# 201944AEP4P02.net
KiCad netlist of a schematic drawn in Altium Designer
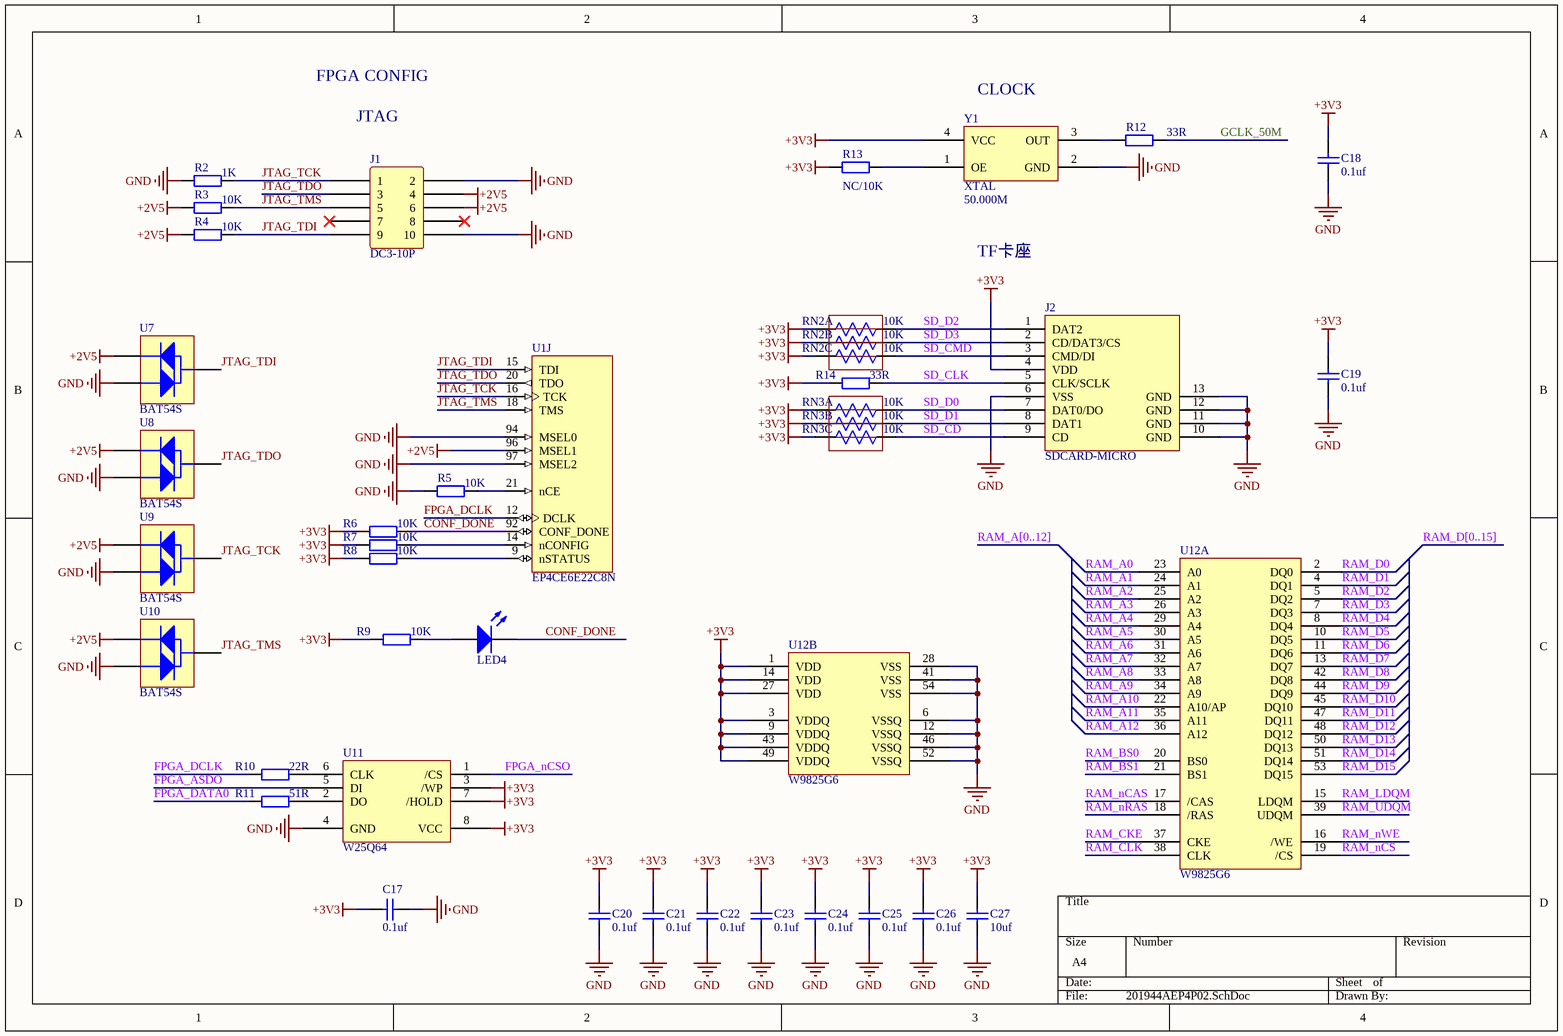
[diagram p0: 201944AEP4P02.SchDoc]

(export (version "E")
  (design (tool "Eeschema 10.0.6"))
  (components
    (comp (ref "C17")
      (value "0.1uf")
      (footprint "C0805")
      (fields (field (name "Comment") "Cap"))
      (libsource (lib "carrot_lib") (part "Cap"))
    )
    (comp (ref "C18")
      (value "0.1uf")
      (footprint "C0805")
      (fields (field (name "Comment") "Cap"))
      (libsource (lib "carrot_lib") (part "Cap"))
    )
    (comp (ref "C19")
      (value "0.1uf")
      (footprint "C0805")
      (fields (field (name "Comment") "Cap"))
      (libsource (lib "carrot_lib") (part "Cap"))
    )
    (comp (ref "C20")
      (value "0.1uf")
      (footprint "C0805")
      (fields (field (name "Comment") "Cap"))
      (libsource (lib "carrot_lib") (part "Cap"))
    )
    (comp (ref "C21")
      (value "0.1uf")
      (footprint "C0805")
      (fields (field (name "Comment") "Cap"))
      (libsource (lib "carrot_lib") (part "Cap"))
    )
    (comp (ref "C22")
      (value "0.1uf")
      (footprint "C0805")
      (fields (field (name "Comment") "Cap"))
      (libsource (lib "carrot_lib") (part "Cap"))
    )
    (comp (ref "C23")
      (value "0.1uf")
      (footprint "C0805")
      (fields (field (name "Comment") "Cap"))
      (libsource (lib "carrot_lib") (part "Cap"))
    )
    (comp (ref "C24")
      (value "0.1uf")
      (footprint "C0805")
      (fields (field (name "Comment") "Cap"))
      (libsource (lib "carrot_lib") (part "Cap"))
    )
    (comp (ref "C25")
      (value "0.1uf")
      (footprint "C0805")
      (fields (field (name "Comment") "Cap"))
      (libsource (lib "carrot_lib") (part "Cap"))
    )
    (comp (ref "C26")
      (value "0.1uf")
      (footprint "C0805")
      (fields (field (name "Comment") "Cap"))
      (libsource (lib "carrot_lib") (part "Cap"))
    )
    (comp (ref "C27")
      (value "10uf")
      (footprint "C0805")
      (fields (field (name "Comment") "Cap"))
      (libsource (lib "carrot_lib") (part "Cap"))
    )
    (comp (ref "J1") (value "DC3-10P") (footprint "DC3-10P") (libsource (lib "carrot_lib") (part "DC3-10P")))
    (comp (ref "J2")
      (value "SDCARD-MICRO")
      (footprint "SDCARD-MICRO")
      (description "Micro SD卡座")
      (libsource (lib "carrot_lib") (part "SDCARD-MICRO"))
    )
    (comp (ref "LED4") (value "LED") (footprint "LED1206") (libsource (lib "carrot_lib") (part "LED")))
    (comp (ref "R2")
      (value "1K")
      (footprint "R0805")
      (fields (field (name "Comment") "Res"))
      (libsource (lib "carrot_lib") (part "Res"))
    )
    (comp (ref "R3")
      (value "10K")
      (footprint "R0805")
      (fields (field (name "Comment") "Res"))
      (libsource (lib "carrot_lib") (part "Res"))
    )
    (comp (ref "R4")
      (value "10K")
      (footprint "R0805")
      (fields (field (name "Comment") "Res"))
      (libsource (lib "carrot_lib") (part "Res"))
    )
    (comp (ref "R5")
      (value "10K")
      (footprint "R0805")
      (fields (field (name "Comment") "Res"))
      (libsource (lib "carrot_lib") (part "Res"))
    )
    (comp (ref "R6")
      (value "10K")
      (footprint "R0805")
      (fields (field (name "Comment") "Res"))
      (libsource (lib "carrot_lib") (part "Res"))
    )
    (comp (ref "R7")
      (value "10K")
      (footprint "R0805")
      (fields (field (name "Comment") "Res"))
      (libsource (lib "carrot_lib") (part "Res"))
    )
    (comp (ref "R8")
      (value "10K")
      (footprint "R0805")
      (fields (field (name "Comment") "Res"))
      (libsource (lib "carrot_lib") (part "Res"))
    )
    (comp (ref "R9")
      (value "10K")
      (footprint "R0805")
      (fields (field (name "Comment") "Res"))
      (libsource (lib "carrot_lib") (part "Res"))
    )
    (comp (ref "R10")
      (value "22R")
      (footprint "R0805")
      (fields (field (name "Comment") "Res"))
      (libsource (lib "carrot_lib") (part "Res"))
    )
    (comp (ref "R11")
      (value "51R")
      (footprint "R0805")
      (fields (field (name "Comment") "Res"))
      (libsource (lib "carrot_lib") (part "Res"))
    )
    (comp (ref "R12")
      (value "33R")
      (footprint "R0805")
      (fields (field (name "Comment") "Res"))
      (libsource (lib "carrot_lib") (part "Res"))
    )
    (comp (ref "R13")
      (value "NC/10K")
      (footprint "R0805")
      (fields (field (name "Comment") "Res"))
      (libsource (lib "carrot_lib") (part "Res"))
    )
    (comp (ref "R14")
      (value "33R")
      (footprint "R0805")
      (fields (field (name "Comment") "Res"))
      (libsource (lib "carrot_lib") (part "Res"))
    )
    (comp (ref "RN2")
      (value "10K")
      (footprint "RA0603")
      (description "贴片排阻")
      (fields (field (name "Comment") "Res Array"))
      (libsource (lib "carrot_lib") (part "Res Array 2"))
    )
    (comp (ref "RN3")
      (value "10K")
      (footprint "RA0603")
      (description "贴片排阻")
      (fields (field (name "Comment") "Res Array"))
      (libsource (lib "carrot_lib") (part "Res Array 2"))
    )
    (comp (ref "U1")
      (value "EP4CE6E22C8N")
      (footprint "EP4CE6E22C8N-EQFP144+")
      (fields (field (name "MANUFACTURER") "Altera"))
      (libsource (lib "carrot_lib") (part "EP4CE6E22C8N"))
    )
    (comp (ref "U7")
      (value "BAT54S")
      (footprint "BAT54S-SOT23")
      (libsource (lib "carrot_lib") (part "BAT54S"))
    )
    (comp (ref "U8")
      (value "BAT54S")
      (footprint "BAT54S-SOT23")
      (libsource (lib "carrot_lib") (part "BAT54S"))
    )
    (comp (ref "U9")
      (value "BAT54S")
      (footprint "BAT54S-SOT23")
      (libsource (lib "carrot_lib") (part "BAT54S"))
    )
    (comp (ref "U10")
      (value "BAT54S")
      (footprint "BAT54S-SOT23")
      (libsource (lib "carrot_lib") (part "BAT54S"))
    )
    (comp (ref "U11")
      (value "W25Q64")
      (footprint "W25Q64-SOIC8")
      (description "64M-BIT\r\nSERIAL FLASH MEMORY WITH\r\nDUAL, QUAD SPI")
      (fields (field (name "MANUFACTURER") "Microchip") (field (name "PARTNUMBER") "24LC256-I/SN"))
      (libsource (lib "carrot_lib") (part "W25Q64"))
    )
    (comp (ref "U12")
      (value "W9825G6")
      (footprint "W9825G6-TSOP54")
      (description "4 M * 4 BANKS * 16 BITS SDRAM")
      (libsource (lib "carrot_lib") (part "W9825G6"))
    )
    (comp (ref "Y1")
      (value "XTAL")
      (footprint "XTAL-3225")
      (description "有源晶振")
      (fields (field (name "ALTIUM_VALUE") "50.000M"))
      (libsource (lib "carrot_lib") (part "XTAL2"))
    )
  )
  (nets
    (net (code "1") (name "+2V5") (class "Default")
      (node (ref "J1") (pin "4") (pinfunction "4_4") (pintype "passive"))
      (node (ref "J1") (pin "6") (pinfunction "6_6") (pintype "passive"))
      (node (ref "R3") (pin "1") (pinfunction "1_1") (pintype "passive"))
      (node (ref "R4") (pin "1") (pinfunction "1_1") (pintype "passive"))
      (node (ref "U1") (pin "96") (pinfunction "MSEL1_96") (pintype "input"))
      (node (ref "U10") (pin "B") (pinfunction "B_B") (pintype "passive"))
      (node (ref "U7") (pin "B") (pinfunction "B_B") (pintype "passive"))
      (node (ref "U8") (pin "B") (pinfunction "B_B") (pintype "passive"))
      (node (ref "U9") (pin "B") (pinfunction "B_B") (pintype "passive"))
    )
    (net (code "2") (name "+3V3") (class "Default")
      (node (ref "C17") (pin "1") (pinfunction "1_1") (pintype "passive"))
      (node (ref "C18") (pin "1") (pinfunction "1_1") (pintype "passive"))
      (node (ref "C19") (pin "1") (pinfunction "1_1") (pintype "passive"))
      (node (ref "C20") (pin "1") (pinfunction "1_1") (pintype "passive"))
      (node (ref "C21") (pin "1") (pinfunction "1_1") (pintype "passive"))
      (node (ref "C22") (pin "1") (pinfunction "1_1") (pintype "passive"))
      (node (ref "C23") (pin "1") (pinfunction "1_1") (pintype "passive"))
      (node (ref "C24") (pin "1") (pinfunction "1_1") (pintype "passive"))
      (node (ref "C25") (pin "1") (pinfunction "1_1") (pintype "passive"))
      (node (ref "C26") (pin "1") (pinfunction "1_1") (pintype "passive"))
      (node (ref "C27") (pin "1") (pinfunction "1_1") (pintype "passive"))
      (node (ref "J2") (pin "4") (pinfunction "VDD_4") (pintype "passive"))
      (node (ref "R13") (pin "1") (pinfunction "1_1") (pintype "passive"))
      (node (ref "R14") (pin "1") (pinfunction "1_1") (pintype "passive"))
      (node (ref "R6") (pin "1") (pinfunction "1_1") (pintype "passive"))
      (node (ref "R7") (pin "1") (pinfunction "1_1") (pintype "passive"))
      (node (ref "R8") (pin "1") (pinfunction "1_1") (pintype "passive"))
      (node (ref "R9") (pin "1") (pinfunction "1_1") (pintype "passive"))
      (node (ref "RN2") (pin "1") (pinfunction "1_1") (pintype "passive"))
      (node (ref "RN2") (pin "2") (pinfunction "2_2") (pintype "passive"))
      (node (ref "RN2") (pin "3") (pinfunction "3_3") (pintype "passive"))
      (node (ref "RN3") (pin "1") (pinfunction "1_1") (pintype "passive"))
      (node (ref "RN3") (pin "2") (pinfunction "2_2") (pintype "passive"))
      (node (ref "RN3") (pin "3") (pinfunction "3_3") (pintype "passive"))
      (node (ref "U11") (pin "3") (pinfunction "/WP_3") (pintype "passive"))
      (node (ref "U11") (pin "7") (pinfunction "/HOLD_7") (pintype "passive"))
      (node (ref "U11") (pin "8") (pinfunction "VCC_8") (pintype "passive"))
      (node (ref "U12") (pin "1") (pinfunction "VDD_1") (pintype "passive"))
      (node (ref "U12") (pin "14") (pinfunction "VDD_14") (pintype "passive"))
      (node (ref "U12") (pin "27") (pinfunction "VDD_27") (pintype "passive"))
      (node (ref "U12") (pin "3") (pinfunction "VDDQ_3") (pintype "passive"))
      (node (ref "U12") (pin "43") (pinfunction "VDDQ_43") (pintype "passive"))
      (node (ref "U12") (pin "49") (pinfunction "VDDQ_49") (pintype "passive"))
      (node (ref "U12") (pin "9") (pinfunction "VDDQ_9") (pintype "passive"))
      (node (ref "Y1") (pin "4") (pinfunction "VCC_4") (pintype "passive"))
    )
    (net (code "3") (name "/CONF_DONE") (class "Default")
      (node (ref "LED4") (pin "2") (pinfunction "K_2") (pintype "passive"))
      (node (ref "R6") (pin "2") (pinfunction "2_2") (pintype "passive"))
      (node (ref "U1") (pin "92") (pinfunction "CONF_DONE_92") (pintype "bidirectional"))
    )
    (net (code "4") (name "/FPGA_ASDO") (class "Default")
      (node (ref "U11") (pin "5") (pinfunction "DI_5") (pintype "passive"))
    )
    (net (code "5") (name "/FPGA_DATA0") (class "Default")
      (node (ref "R11") (pin "1") (pinfunction "1_1") (pintype "passive"))
    )
    (net (code "6") (name "/FPGA_DCLK") (class "Default")
      (node (ref "R10") (pin "1") (pinfunction "1_1") (pintype "passive"))
      (node (ref "U1") (pin "12") (pinfunction "DCLK_12") (pintype "bidirectional"))
    )
    (net (code "7") (name "/FPGA_nCSO") (class "Default")
      (node (ref "U11") (pin "1") (pinfunction "/CS_1") (pintype "passive"))
    )
    (net (code "8") (name "/GCLK_50M") (class "Default")
      (node (ref "R12") (pin "2") (pinfunction "2_2") (pintype "passive"))
    )
    (net (code "9") (name "/JTAG_TCK") (class "Default")
      (node (ref "J1") (pin "1") (pinfunction "1_1") (pintype "passive"))
      (node (ref "R2") (pin "2") (pinfunction "2_2") (pintype "passive"))
      (node (ref "U1") (pin "16") (pinfunction "TCK_16") (pintype "input"))
      (node (ref "U9") (pin "C") (pinfunction "C_C") (pintype "passive"))
    )
    (net (code "10") (name "/JTAG_TDI") (class "Default")
      (node (ref "J1") (pin "9") (pinfunction "9_9") (pintype "passive"))
      (node (ref "R4") (pin "2") (pinfunction "2_2") (pintype "passive"))
      (node (ref "U1") (pin "15") (pinfunction "TDI_15") (pintype "input"))
      (node (ref "U7") (pin "C") (pinfunction "C_C") (pintype "passive"))
    )
    (net (code "11") (name "/JTAG_TDO") (class "Default")
      (node (ref "J1") (pin "3") (pinfunction "3_3") (pintype "passive"))
      (node (ref "U1") (pin "20") (pinfunction "TDO_20") (pintype "output"))
      (node (ref "U8") (pin "C") (pinfunction "C_C") (pintype "passive"))
    )
    (net (code "12") (name "/JTAG_TMS") (class "Default")
      (node (ref "J1") (pin "5") (pinfunction "5_5") (pintype "passive"))
      (node (ref "R3") (pin "2") (pinfunction "2_2") (pintype "passive"))
      (node (ref "U1") (pin "18") (pinfunction "TMS_18") (pintype "input"))
      (node (ref "U10") (pin "C") (pinfunction "C_C") (pintype "passive"))
    )
    (net (code "13") (name "/RAM_A0") (class "Default")
      (node (ref "U12") (pin "23") (pinfunction "A0_23") (pintype "passive"))
    )
    (net (code "14") (name "/RAM_A1") (class "Default")
      (node (ref "U12") (pin "24") (pinfunction "A1_24") (pintype "passive"))
    )
    (net (code "15") (name "/RAM_A2") (class "Default")
      (node (ref "U12") (pin "25") (pinfunction "A2_25") (pintype "passive"))
    )
    (net (code "16") (name "/RAM_A3") (class "Default")
      (node (ref "U12") (pin "26") (pinfunction "A3_26") (pintype "passive"))
    )
    (net (code "17") (name "/RAM_A4") (class "Default")
      (node (ref "U12") (pin "29") (pinfunction "A4_29") (pintype "passive"))
    )
    (net (code "18") (name "/RAM_A5") (class "Default")
      (node (ref "U12") (pin "30") (pinfunction "A5_30") (pintype "passive"))
    )
    (net (code "19") (name "/RAM_A6") (class "Default")
      (node (ref "U12") (pin "31") (pinfunction "A6_31") (pintype "passive"))
    )
    (net (code "20") (name "/RAM_A7") (class "Default")
      (node (ref "U12") (pin "32") (pinfunction "A7_32") (pintype "passive"))
    )
    (net (code "21") (name "/RAM_A8") (class "Default")
      (node (ref "U12") (pin "33") (pinfunction "A8_33") (pintype "passive"))
    )
    (net (code "22") (name "/RAM_A9") (class "Default")
      (node (ref "U12") (pin "34") (pinfunction "A9_34") (pintype "passive"))
    )
    (net (code "23") (name "/RAM_A10") (class "Default")
      (node (ref "U12") (pin "22") (pinfunction "A10/AP_22") (pintype "passive"))
    )
    (net (code "24") (name "/RAM_A11") (class "Default")
      (node (ref "U12") (pin "35") (pinfunction "A11_35") (pintype "passive"))
    )
    (net (code "25") (name "/RAM_A12") (class "Default")
      (node (ref "U12") (pin "36") (pinfunction "A12_36") (pintype "passive"))
    )
    (net (code "27") (name "/RAM_BS0") (class "Default")
      (node (ref "U12") (pin "20") (pinfunction "BS0_20") (pintype "passive"))
    )
    (net (code "28") (name "/RAM_BS1") (class "Default")
      (node (ref "U12") (pin "21") (pinfunction "BS1_21") (pintype "passive"))
    )
    (net (code "29") (name "/RAM_CKE") (class "Default")
      (node (ref "U12") (pin "37") (pinfunction "CKE_37") (pintype "passive"))
    )
    (net (code "30") (name "/RAM_CLK") (class "Default")
      (node (ref "U12") (pin "38") (pinfunction "CLK_38") (pintype "passive"))
    )
    (net (code "31") (name "/RAM_D0") (class "Default")
      (node (ref "U12") (pin "2") (pinfunction "DQ0_2") (pintype "passive"))
    )
    (net (code "32") (name "/RAM_D1") (class "Default")
      (node (ref "U12") (pin "4") (pinfunction "DQ1_4") (pintype "passive"))
    )
    (net (code "33") (name "/RAM_D2") (class "Default")
      (node (ref "U12") (pin "5") (pinfunction "DQ2_5") (pintype "passive"))
    )
    (net (code "34") (name "/RAM_D3") (class "Default")
      (node (ref "U12") (pin "7") (pinfunction "DQ3_7") (pintype "passive"))
    )
    (net (code "35") (name "/RAM_D4") (class "Default")
      (node (ref "U12") (pin "8") (pinfunction "DQ4_8") (pintype "passive"))
    )
    (net (code "36") (name "/RAM_D5") (class "Default")
      (node (ref "U12") (pin "10") (pinfunction "DQ5_10") (pintype "passive"))
    )
    (net (code "37") (name "/RAM_D6") (class "Default")
      (node (ref "U12") (pin "11") (pinfunction "DQ6_11") (pintype "passive"))
    )
    (net (code "38") (name "/RAM_D7") (class "Default")
      (node (ref "U12") (pin "13") (pinfunction "DQ7_13") (pintype "passive"))
    )
    (net (code "39") (name "/RAM_D8") (class "Default")
      (node (ref "U12") (pin "42") (pinfunction "DQ8_42") (pintype "passive"))
    )
    (net (code "40") (name "/RAM_D9") (class "Default")
      (node (ref "U12") (pin "44") (pinfunction "DQ9_44") (pintype "passive"))
    )
    (net (code "41") (name "/RAM_D10") (class "Default")
      (node (ref "U12") (pin "45") (pinfunction "DQ10_45") (pintype "passive"))
    )
    (net (code "42") (name "/RAM_D11") (class "Default")
      (node (ref "U12") (pin "47") (pinfunction "DQ11_47") (pintype "passive"))
    )
    (net (code "43") (name "/RAM_D12") (class "Default")
      (node (ref "U12") (pin "48") (pinfunction "DQ12_48") (pintype "passive"))
    )
    (net (code "44") (name "/RAM_D13") (class "Default")
      (node (ref "U12") (pin "50") (pinfunction "DQ13_50") (pintype "passive"))
    )
    (net (code "45") (name "/RAM_D14") (class "Default")
      (node (ref "U12") (pin "51") (pinfunction "DQ14_51") (pintype "passive"))
    )
    (net (code "46") (name "/RAM_D15") (class "Default")
      (node (ref "U12") (pin "53") (pinfunction "DQ15_53") (pintype "passive"))
    )
    (net (code "48") (name "/RAM_LDQM") (class "Default")
      (node (ref "U12") (pin "15") (pinfunction "LDQM_15") (pintype "passive"))
    )
    (net (code "49") (name "/RAM_UDQM") (class "Default")
      (node (ref "U12") (pin "39") (pinfunction "UDQM_39") (pintype "passive"))
    )
    (net (code "50") (name "/RAM_nCAS") (class "Default")
      (node (ref "U12") (pin "17") (pinfunction "/CAS_17") (pintype "passive"))
    )
    (net (code "51") (name "/RAM_nCS") (class "Default")
      (node (ref "U12") (pin "19") (pinfunction "/CS_19") (pintype "passive"))
    )
    (net (code "52") (name "/RAM_nRAS") (class "Default")
      (node (ref "U12") (pin "18") (pinfunction "/RAS_18") (pintype "passive"))
    )
    (net (code "53") (name "/RAM_nWE") (class "Default")
      (node (ref "U12") (pin "16") (pinfunction "/WE_16") (pintype "passive"))
    )
    (net (code "54") (name "/SD_CD") (class "Default")
      (node (ref "J2") (pin "9") (pinfunction "CD_9") (pintype "passive"))
      (node (ref "RN3") (pin "6") (pinfunction "6_6") (pintype "passive"))
    )
    (net (code "55") (name "/SD_CLK") (class "Default")
      (node (ref "J2") (pin "5") (pinfunction "CLK/SCLK_5") (pintype "passive"))
      (node (ref "R14") (pin "2") (pinfunction "2_2") (pintype "passive"))
    )
    (net (code "56") (name "/SD_CMD") (class "Default")
      (node (ref "J2") (pin "3") (pinfunction "CMD/DI_3") (pintype "passive"))
      (node (ref "RN2") (pin "6") (pinfunction "6_6") (pintype "passive"))
    )
    (net (code "57") (name "/SD_D0") (class "Default")
      (node (ref "J2") (pin "7") (pinfunction "DAT0/DO_7") (pintype "passive"))
      (node (ref "RN3") (pin "8") (pinfunction "8_8") (pintype "passive"))
    )
    (net (code "58") (name "/SD_D1") (class "Default")
      (node (ref "J2") (pin "8") (pinfunction "DAT1_8") (pintype "passive"))
      (node (ref "RN3") (pin "7") (pinfunction "7_7") (pintype "passive"))
    )
    (net (code "59") (name "/SD_D2") (class "Default")
      (node (ref "J2") (pin "1") (pinfunction "DAT2_1") (pintype "passive"))
      (node (ref "RN2") (pin "8") (pinfunction "8_8") (pintype "passive"))
    )
    (net (code "60") (name "/SD_D3") (class "Default")
      (node (ref "J2") (pin "2") (pinfunction "CD/DAT3/CS_2") (pintype "passive"))
      (node (ref "RN2") (pin "7") (pinfunction "7_7") (pintype "passive"))
    )
    (net (code "61") (name "GND") (class "Default")
      (node (ref "C17") (pin "2") (pinfunction "2_2") (pintype "passive"))
      (node (ref "C18") (pin "2") (pinfunction "2_2") (pintype "passive"))
      (node (ref "C19") (pin "2") (pinfunction "2_2") (pintype "passive"))
      (node (ref "C20") (pin "2") (pinfunction "2_2") (pintype "passive"))
      (node (ref "C21") (pin "2") (pinfunction "2_2") (pintype "passive"))
      (node (ref "C22") (pin "2") (pinfunction "2_2") (pintype "passive"))
      (node (ref "C23") (pin "2") (pinfunction "2_2") (pintype "passive"))
      (node (ref "C24") (pin "2") (pinfunction "2_2") (pintype "passive"))
      (node (ref "C25") (pin "2") (pinfunction "2_2") (pintype "passive"))
      (node (ref "C26") (pin "2") (pinfunction "2_2") (pintype "passive"))
      (node (ref "C27") (pin "2") (pinfunction "2_2") (pintype "passive"))
      (node (ref "J1") (pin "10") (pinfunction "10_10") (pintype "passive"))
      (node (ref "J1") (pin "2") (pinfunction "2_2") (pintype "passive"))
      (node (ref "J2") (pin "10") (pinfunction "GND_10") (pintype "passive"))
      (node (ref "J2") (pin "11") (pinfunction "GND_11") (pintype "passive"))
      (node (ref "J2") (pin "12") (pinfunction "GND_12") (pintype "passive"))
      (node (ref "J2") (pin "13") (pinfunction "GND_13") (pintype "passive"))
      (node (ref "J2") (pin "6") (pinfunction "VSS_6") (pintype "passive"))
      (node (ref "R2") (pin "1") (pinfunction "1_1") (pintype "passive"))
      (node (ref "R5") (pin "1") (pinfunction "1_1") (pintype "passive"))
      (node (ref "U1") (pin "94") (pinfunction "MSEL0_94") (pintype "input"))
      (node (ref "U1") (pin "97") (pinfunction "MSEL2_97") (pintype "input"))
      (node (ref "U10") (pin "A") (pinfunction "A_A") (pintype "passive"))
      (node (ref "U11") (pin "4") (pinfunction "GND_4") (pintype "passive"))
      (node (ref "U12") (pin "12") (pinfunction "VSSQ_12") (pintype "passive"))
      (node (ref "U12") (pin "28") (pinfunction "VSS_28") (pintype "passive"))
      (node (ref "U12") (pin "41") (pinfunction "VSS_41") (pintype "passive"))
      (node (ref "U12") (pin "46") (pinfunction "VSSQ_46") (pintype "passive"))
      (node (ref "U12") (pin "52") (pinfunction "VSSQ_52") (pintype "passive"))
      (node (ref "U12") (pin "54") (pinfunction "VSS_54") (pintype "passive"))
      (node (ref "U12") (pin "6") (pinfunction "VSSQ_6") (pintype "passive"))
      (node (ref "U7") (pin "A") (pinfunction "A_A") (pintype "passive"))
      (node (ref "U8") (pin "A") (pinfunction "A_A") (pintype "passive"))
      (node (ref "U9") (pin "A") (pinfunction "A_A") (pintype "passive"))
      (node (ref "Y1") (pin "2") (pinfunction "GND_2") (pintype "passive"))
    )
    (net (code "62") (name "Net-(LED4-A)") (class "Default")
      (node (ref "LED4") (pin "1") (pinfunction "A_1") (pintype "passive"))
      (node (ref "R9") (pin "2") (pinfunction "2_2") (pintype "passive"))
    )
    (net (code "63") (name "Net-(U1J-nCE)") (class "Default")
      (node (ref "R5") (pin "2") (pinfunction "2_2") (pintype "passive"))
      (node (ref "U1") (pin "21") (pinfunction "nCE_21") (pintype "input"))
    )
    (net (code "64") (name "Net-(U1J-nCONFIG)") (class "Default")
      (node (ref "R7") (pin "2") (pinfunction "2_2") (pintype "passive"))
      (node (ref "U1") (pin "14") (pinfunction "nCONFIG_14") (pintype "input"))
    )
    (net (code "65") (name "Net-(U1J-nSTATUS)") (class "Default")
      (node (ref "R8") (pin "2") (pinfunction "2_2") (pintype "passive"))
      (node (ref "U1") (pin "9") (pinfunction "nSTATUS_9") (pintype "bidirectional"))
    )
    (net (code "66") (name "Net-(U11-CLK)") (class "Default")
      (node (ref "R10") (pin "2") (pinfunction "2_2") (pintype "passive"))
      (node (ref "U11") (pin "6") (pinfunction "CLK_6") (pintype "passive"))
    )
    (net (code "67") (name "Net-(U11-DO)") (class "Default")
      (node (ref "R11") (pin "2") (pinfunction "2_2") (pintype "passive"))
      (node (ref "U11") (pin "2") (pinfunction "DO_2") (pintype "passive"))
    )
    (net (code "68") (name "Net-(Y1-OE)") (class "Default")
      (node (ref "R13") (pin "2") (pinfunction "2_2") (pintype "passive"))
      (node (ref "Y1") (pin "1") (pinfunction "OE_1") (pintype "passive"))
    )
    (net (code "69") (name "Net-(Y1-OUT)") (class "Default")
      (node (ref "R12") (pin "1") (pinfunction "1_1") (pintype "passive"))
      (node (ref "Y1") (pin "3") (pinfunction "OUT_3") (pintype "passive"))
    )
    (net (code "70") (name "unconnected-(J1-Pad7)") (class "Default")
      (node (ref "J1") (pin "7") (pinfunction "7_7") (pintype "passive+no_connect"))
    )
    (net (code "71") (name "unconnected-(J1-Pad8)") (class "Default")
      (node (ref "J1") (pin "8") (pinfunction "8_8") (pintype "passive+no_connect"))
    )
  )
)
